# 5_USB-RTC-RST.net
KiCad netlist of a schematic drawn in Altium Designer
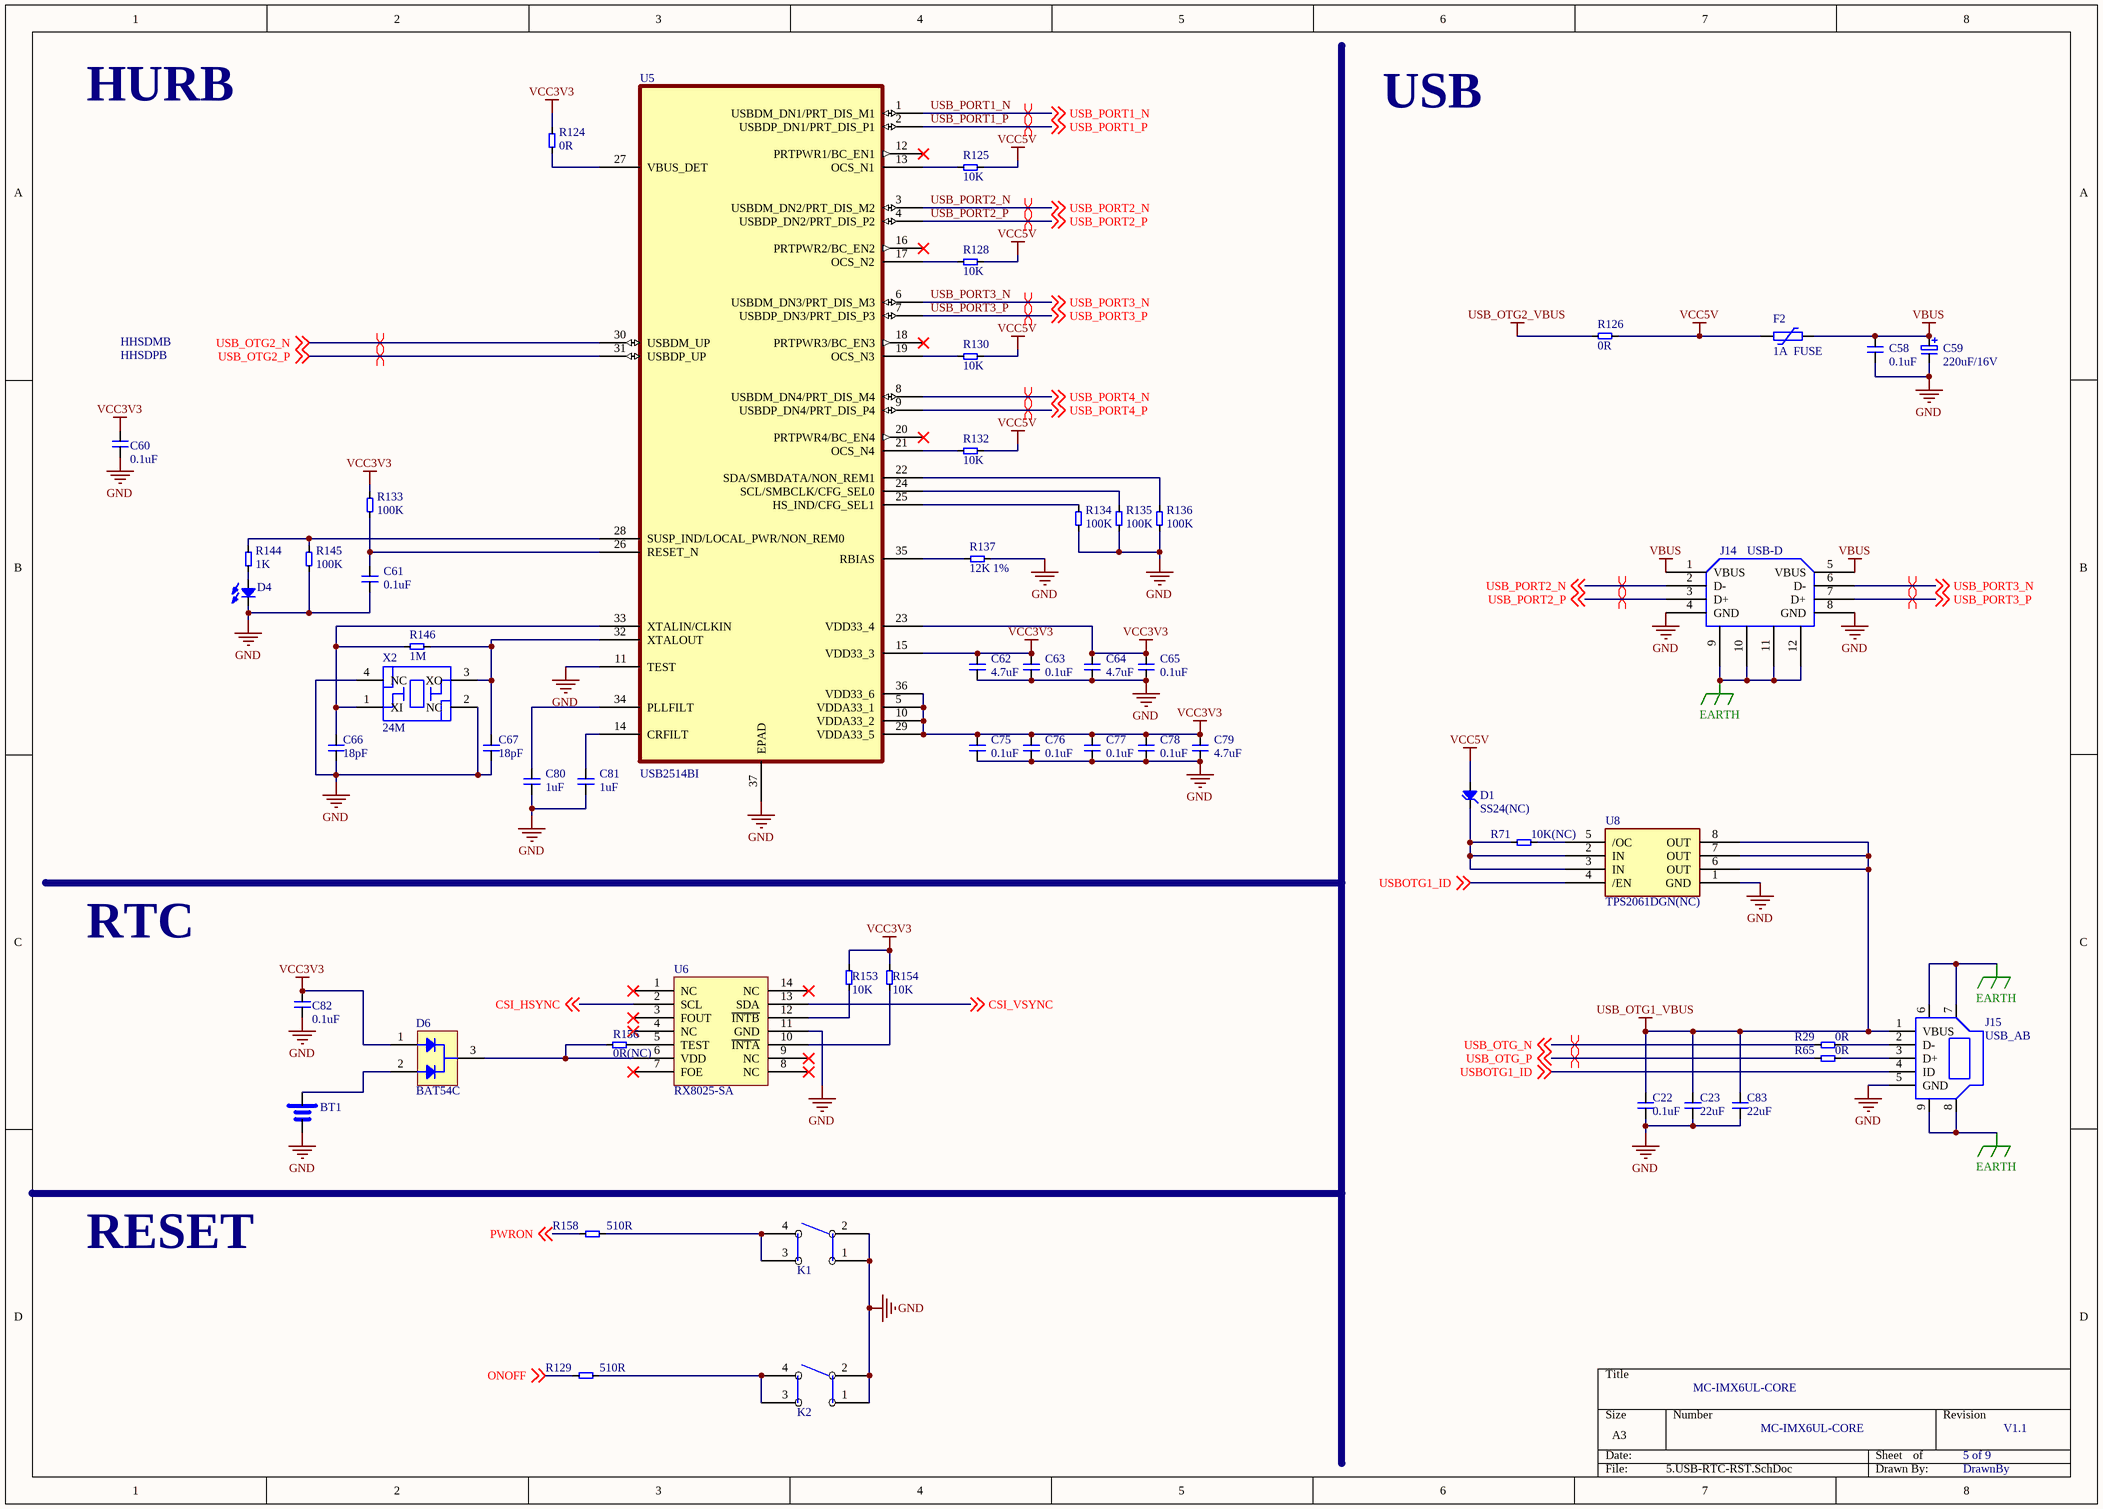
[diagram p0: 5.USB-RTC-RST.SchDoc]

(export (version "E")
  (design (tool "Eeschema 10.0.6"))
  (components
    (comp (ref "BT1") (value "~") (footprint "CR1220") (libsource (lib "LDT-SCH") (part "电池")))
    (comp (ref "C22")
      (value "0.1uF")
      (footprint "0603C")
      (description "电容")
      (libsource (lib "*") (part "电容"))
    )
    (comp (ref "C23") (value "22uF") (footprint "0805C") (description "电容") (libsource (lib "*") (part "电容")))
    (comp (ref "C58")
      (value "0.1uF")
      (footprint "0603C")
      (description "电容")
      (libsource (lib "*") (part "电容"))
    )
    (comp (ref "C59")
      (value "220uF/16V")
      (footprint "RAD-3/6")
      (description "直插电解电容")
      (libsource (lib "*") (part "直插电解电容"))
    )
    (comp (ref "C60")
      (value "0.1uF")
      (footprint "0603C")
      (description "电容")
      (libsource (lib "*") (part "电容"))
    )
    (comp (ref "C61")
      (value "0.1uF")
      (footprint "0603C")
      (description "电容")
      (libsource (lib "*") (part "电容"))
    )
    (comp (ref "C62")
      (value "4.7uF")
      (footprint "0603C")
      (description "电容")
      (libsource (lib "*") (part "电容"))
    )
    (comp (ref "C63")
      (value "0.1uF")
      (footprint "0603C")
      (description "电容")
      (libsource (lib "*") (part "电容"))
    )
    (comp (ref "C64")
      (value "4.7uF")
      (footprint "0603C")
      (description "电容")
      (libsource (lib "*") (part "电容"))
    )
    (comp (ref "C65")
      (value "0.1uF")
      (footprint "0603C")
      (description "电容")
      (libsource (lib "*") (part "电容"))
    )
    (comp (ref "C66") (value "18pF") (footprint "0603C") (description "电容") (libsource (lib "*") (part "电容")))
    (comp (ref "C67") (value "18pF") (footprint "0603C") (description "电容") (libsource (lib "*") (part "电容")))
    (comp (ref "C75")
      (value "0.1uF")
      (footprint "0603C")
      (description "电容")
      (libsource (lib "*") (part "电容"))
    )
    (comp (ref "C76")
      (value "0.1uF")
      (footprint "0603C")
      (description "电容")
      (libsource (lib "*") (part "电容"))
    )
    (comp (ref "C77")
      (value "0.1uF")
      (footprint "0603C")
      (description "电容")
      (libsource (lib "*") (part "电容"))
    )
    (comp (ref "C78")
      (value "0.1uF")
      (footprint "0603C")
      (description "电容")
      (libsource (lib "*") (part "电容"))
    )
    (comp (ref "C79")
      (value "4.7uF")
      (footprint "0603C")
      (description "电容")
      (libsource (lib "*") (part "电容"))
    )
    (comp (ref "C80") (value "1uF") (footprint "0603C") (description "电容") (libsource (lib "*") (part "电容")))
    (comp (ref "C81") (value "1uF") (footprint "0603C") (description "电容") (libsource (lib "*") (part "电容")))
    (comp (ref "C82")
      (value "0.1uF")
      (footprint "0603C")
      (description "电容")
      (libsource (lib "*") (part "电容"))
    )
    (comp (ref "C83") (value "22uF") (footprint "0805C") (description "电容") (libsource (lib "*") (part "电容")))
    (comp (ref "D1") (value "SS24(NC)") (footprint "SMA") (libsource (lib "LDT-SCH") (part "SS24")))
    (comp (ref "D4") (value "发光二极管") (footprint "0603D") (libsource (lib "LDT-SCH") (part "发光二极管")))
    (comp (ref "D6")
      (value "BAT54C")
      (footprint "SOT-23")
      (description "SCHOTTKY DIODE")
      (libsource (lib "LDT-SCH") (part "BAT54C"))
    )
    (comp (ref "F2")
      (value "1A  FUSE")
      (footprint "1812F")
      (description "贴片自恢复保险丝")
      (libsource (lib "LDT-SCH") (part "FUSE"))
    )
    (comp (ref "J14")
      (value "USB-D")
      (footprint "USB-D")
      (description "USB DOUBLE PORTS")
      (libsource (lib "LDT-SCH") (part "USB-D"))
    )
    (comp (ref "J15")
      (value "USB_AB")
      (footprint "USB-AB")
      (description "小USB插痤")
      (libsource (lib "LDT-SCH") (part "USB_AB"))
    )
    (comp (ref "K1") (value "按键") (footprint "SS-SPB-4.5") (libsource (lib "LDT-SCH") (part "按键")))
    (comp (ref "K2") (value "按键") (footprint "SS-SPB-4.5") (libsource (lib "LDT-SCH") (part "按键")))
    (comp (ref "R29")
      (value "0R")
      (footprint "0603R")
      (description "电阻")
      (libsource (lib "LDT-SCH") (part "电阻"))
    )
    (comp (ref "R65")
      (value "0R")
      (footprint "0603R")
      (description "电阻")
      (libsource (lib "LDT-SCH") (part "电阻"))
    )
    (comp (ref "R71")
      (value "10K(NC)")
      (footprint "0603R")
      (description "电阻")
      (libsource (lib "LDT-SCH") (part "电阻"))
    )
    (comp (ref "R124")
      (value "0R")
      (footprint "0603R")
      (description "电阻")
      (libsource (lib "LDT-SCH") (part "电阻"))
    )
    (comp (ref "R125")
      (value "10K")
      (footprint "0603R")
      (description "电阻")
      (libsource (lib "LDT-SCH") (part "电阻"))
    )
    (comp (ref "R126") (value "0R") (footprint "0603R") (description "电阻") (libsource (lib "*") (part "电阻")))
    (comp (ref "R128")
      (value "10K")
      (footprint "0603R")
      (description "电阻")
      (libsource (lib "LDT-SCH") (part "电阻"))
    )
    (comp (ref "R129")
      (value "510R")
      (footprint "0603R")
      (description "电阻")
      (libsource (lib "*") (part "电阻"))
    )
    (comp (ref "R130")
      (value "10K")
      (footprint "0603R")
      (description "电阻")
      (libsource (lib "LDT-SCH") (part "电阻"))
    )
    (comp (ref "R132")
      (value "10K")
      (footprint "0603R")
      (description "电阻")
      (libsource (lib "LDT-SCH") (part "电阻"))
    )
    (comp (ref "R133")
      (value "100K")
      (footprint "0603R")
      (description "电阻")
      (libsource (lib "LDT-SCH") (part "电阻"))
    )
    (comp (ref "R134")
      (value "100K")
      (footprint "0603R")
      (description "电阻")
      (libsource (lib "LDT-SCH") (part "电阻"))
    )
    (comp (ref "R135")
      (value "100K")
      (footprint "0603R")
      (description "电阻")
      (libsource (lib "LDT-SCH") (part "电阻"))
    )
    (comp (ref "R136")
      (value "100K")
      (footprint "0603R")
      (description "电阻")
      (libsource (lib "LDT-SCH") (part "电阻"))
    )
    (comp (ref "R137")
      (value "12K 1%")
      (footprint "0603R")
      (description "电阻")
      (libsource (lib "LDT-SCH") (part "电阻"))
    )
    (comp (ref "R144")
      (value "1K")
      (footprint "0603R")
      (description "电阻")
      (libsource (lib "LDT-SCH") (part "电阻"))
    )
    (comp (ref "R145")
      (value "100K")
      (footprint "0603R")
      (description "电阻")
      (libsource (lib "LDT-SCH") (part "电阻"))
    )
    (comp (ref "R146")
      (value "1M")
      (footprint "0603R")
      (description "电阻")
      (libsource (lib "LDT-SCH") (part "电阻"))
    )
    (comp (ref "R153") (value "10K") (footprint "0603R") (description "电阻") (libsource (lib "*") (part "电阻")))
    (comp (ref "R154") (value "10K") (footprint "0603R") (description "电阻") (libsource (lib "*") (part "电阻")))
    (comp (ref "R156")
      (value "0R(NC)")
      (footprint "0603R")
      (description "电阻")
      (libsource (lib "*") (part "电阻"))
    )
    (comp (ref "R158")
      (value "510R")
      (footprint "0603R")
      (description "电阻")
      (libsource (lib "*") (part "电阻"))
    )
    (comp (ref "U5")
      (value "USB2514BI")
      (footprint "QFN-36")
      (description "USB2514Bi")
      (libsource (lib "LDT-SCH") (part "USB2514"))
    )
    (comp (ref "U6")
      (value "RX8025-SA")
      (footprint "SOP14-1.27")
      (description "I2C interface RTC with crystal built-in")
      (libsource (lib "*") (part "RX8025-SA"))
    )
    (comp (ref "U8")
      (value "TPS2061DGN(NC)")
      (footprint "MSOP-8")
      (description "TPS2061DGN")
      (libsource (lib "LDT-SCH") (part "TPS2061"))
    )
    (comp (ref "X2")
      (value "24M")
      (footprint "OSC4-3225")
      (description "4PIN表贴晶体")
      (libsource (lib "LDT-SCH") (part "表贴晶体"))
    )
  )
  (nets
    (net (code "1") (name "CSI_HSYNC") (class "Default")
      (node (ref "U6") (pin "2") (pinfunction "SCL_2") (pintype "passive"))
    )
    (net (code "2") (name "CSI_VSYNC") (class "Default")
      (node (ref "U6") (pin "13") (pinfunction "SDA_13") (pintype "passive"))
    )
    (net (code "3") (name "EARTH") (class "Default")
      (node (ref "J14") (pin "10") (pintype "passive"))
      (node (ref "J14") (pin "11") (pintype "passive"))
      (node (ref "J14") (pin "12") (pintype "passive"))
      (node (ref "J14") (pin "9") (pintype "passive"))
      (node (ref "J15") (pin "6") (pinfunction "GND_6") (pintype "passive"))
      (node (ref "J15") (pin "7") (pinfunction "GND_7") (pintype "passive"))
      (node (ref "J15") (pin "8") (pinfunction "GND_8") (pintype "passive"))
      (node (ref "J15") (pin "9") (pinfunction "GND_9") (pintype "passive"))
    )
    (net (code "4") (name "GND") (class "Default")
      (node (ref "BT1") (pin "2") (pintype "passive"))
      (node (ref "C22") (pin "1") (pintype "passive"))
      (node (ref "C23") (pin "1") (pintype "passive"))
      (node (ref "C58") (pin "1") (pintype "passive"))
      (node (ref "C59") (pin "2") (pintype "passive"))
      (node (ref "C60") (pin "1") (pintype "passive"))
      (node (ref "C61") (pin "1") (pintype "passive"))
      (node (ref "C62") (pin "1") (pintype "passive"))
      (node (ref "C63") (pin "1") (pintype "passive"))
      (node (ref "C64") (pin "1") (pintype "passive"))
      (node (ref "C65") (pin "1") (pintype "passive"))
      (node (ref "C66") (pin "1") (pintype "passive"))
      (node (ref "C67") (pin "1") (pintype "passive"))
      (node (ref "C75") (pin "1") (pintype "passive"))
      (node (ref "C76") (pin "1") (pintype "passive"))
      (node (ref "C77") (pin "1") (pintype "passive"))
      (node (ref "C78") (pin "1") (pintype "passive"))
      (node (ref "C79") (pin "1") (pintype "passive"))
      (node (ref "C80") (pin "1") (pintype "passive"))
      (node (ref "C81") (pin "1") (pintype "passive"))
      (node (ref "C82") (pin "1") (pintype "passive"))
      (node (ref "C83") (pin "1") (pintype "passive"))
      (node (ref "D4") (pin "K") (pintype "passive"))
      (node (ref "J14") (pin "4") (pinfunction "GND_4") (pintype "passive"))
      (node (ref "J14") (pin "8") (pinfunction "GND_8") (pintype "passive"))
      (node (ref "J15") (pin "5") (pinfunction "GND_5") (pintype "passive"))
      (node (ref "K1") (pin "1") (pinfunction "1_1") (pintype "passive"))
      (node (ref "K1") (pin "2") (pinfunction "2_2") (pintype "passive"))
      (node (ref "K2") (pin "1") (pinfunction "1_1") (pintype "passive"))
      (node (ref "K2") (pin "2") (pinfunction "2_2") (pintype "passive"))
      (node (ref "R134") (pin "2") (pintype "passive"))
      (node (ref "R135") (pin "2") (pintype "passive"))
      (node (ref "R136") (pin "2") (pintype "passive"))
      (node (ref "R137") (pin "1") (pintype "passive"))
      (node (ref "R145") (pin "2") (pintype "passive"))
      (node (ref "U5") (pin "11") (pinfunction "TEST_11") (pintype "passive"))
      (node (ref "U5") (pin "37") (pinfunction "EPAD_37") (pintype "passive"))
      (node (ref "U6") (pin "11") (pinfunction "GND_11") (pintype "passive"))
      (node (ref "U8") (pin "1") (pinfunction "GND_1") (pintype "passive"))
      (node (ref "X2") (pin "2") (pinfunction "NC_2") (pintype "passive"))
      (node (ref "X2") (pin "4") (pinfunction "NC_4") (pintype "passive"))
    )
    (net (code "5") (name "Net-(BT1-Pad1)") (class "Default")
      (node (ref "BT1") (pin "1") (pintype "passive"))
      (node (ref "D6") (pin "2") (pinfunction "2_2") (pintype "passive"))
    )
    (net (code "6") (name "Net-(D1-PadK)") (class "Default")
      (node (ref "D1") (pin "K") (pintype "passive"))
      (node (ref "R71") (pin "2") (pintype "passive"))
      (node (ref "U8") (pin "2") (pinfunction "IN_2") (pintype "passive"))
      (node (ref "U8") (pin "3") (pinfunction "IN_3") (pintype "passive"))
    )
    (net (code "7") (name "Net-(D4-PadA)") (class "Default")
      (node (ref "D4") (pin "A") (pintype "passive"))
      (node (ref "R144") (pin "1") (pintype "passive"))
    )
    (net (code "8") (name "Net-(J15-D+)") (class "Default")
      (node (ref "J15") (pin "3") (pinfunction "D+_3") (pintype "passive"))
      (node (ref "R65") (pin "1") (pintype "passive"))
    )
    (net (code "9") (name "Net-(J15-D-)") (class "Default")
      (node (ref "J15") (pin "2") (pinfunction "D-_2") (pintype "passive"))
      (node (ref "R29") (pin "1") (pintype "passive"))
    )
    (net (code "10") (name "Net-(K1-Pad3)") (class "Default")
      (node (ref "K1") (pin "3") (pinfunction "3_3") (pintype "passive"))
      (node (ref "K1") (pin "4") (pinfunction "4_4") (pintype "passive"))
      (node (ref "R158") (pin "1") (pintype "passive"))
    )
    (net (code "11") (name "Net-(K2-Pad3)") (class "Default")
      (node (ref "K2") (pin "3") (pinfunction "3_3") (pintype "passive"))
      (node (ref "K2") (pin "4") (pinfunction "4_4") (pintype "passive"))
      (node (ref "R129") (pin "1") (pintype "passive"))
    )
    (net (code "12") (name "Net-(U5-CRFILT)") (class "Default")
      (node (ref "C81") (pin "2") (pintype "passive"))
      (node (ref "U5") (pin "14") (pinfunction "CRFILT_14") (pintype "passive"))
    )
    (net (code "13") (name "Net-(U5-HS_IND{slash}CFG_SEL1)") (class "Default")
      (node (ref "R134") (pin "1") (pintype "passive"))
      (node (ref "U5") (pin "25") (pinfunction "HS_IND/CFG_SEL1_25") (pintype "passive"))
    )
    (net (code "14") (name "Net-(U5-OCS_N1)") (class "Default")
      (node (ref "R125") (pin "2") (pintype "passive"))
      (node (ref "U5") (pin "13") (pinfunction "OCS_N1_13") (pintype "passive"))
    )
    (net (code "15") (name "Net-(U5-OCS_N2)") (class "Default")
      (node (ref "R128") (pin "2") (pintype "passive"))
      (node (ref "U5") (pin "17") (pinfunction "OCS_N2_17") (pintype "passive"))
    )
    (net (code "16") (name "Net-(U5-OCS_N3)") (class "Default")
      (node (ref "R130") (pin "2") (pintype "passive"))
      (node (ref "U5") (pin "19") (pinfunction "OCS_N3_19") (pintype "passive"))
    )
    (net (code "17") (name "Net-(U5-OCS_N4)") (class "Default")
      (node (ref "R132") (pin "2") (pintype "passive"))
      (node (ref "U5") (pin "21") (pinfunction "OCS_N4_21") (pintype "passive"))
    )
    (net (code "18") (name "Net-(U5-PLLFILT)") (class "Default")
      (node (ref "C80") (pin "2") (pintype "passive"))
      (node (ref "U5") (pin "34") (pinfunction "PLLFILT_34") (pintype "passive"))
    )
    (net (code "19") (name "Net-(U5-RBIAS)") (class "Default")
      (node (ref "R137") (pin "2") (pintype "passive"))
      (node (ref "U5") (pin "35") (pinfunction "RBIAS_35") (pintype "passive"))
    )
    (net (code "20") (name "Net-(U5-RESET_N)") (class "Default")
      (node (ref "C61") (pin "2") (pintype "passive"))
      (node (ref "R133") (pin "2") (pintype "passive"))
      (node (ref "U5") (pin "26") (pinfunction "RESET_N_26") (pintype "passive"))
    )
    (net (code "21") (name "Net-(U5-SCL{slash}SMBCLK{slash}CFG_SEL0)") (class "Default")
      (node (ref "R135") (pin "1") (pintype "passive"))
      (node (ref "U5") (pin "24") (pinfunction "SCL/SMBCLK/CFG_SEL0_24") (pintype "passive"))
    )
    (net (code "22") (name "Net-(U5-SDA{slash}SMBDATA{slash}NON_REM1)") (class "Default")
      (node (ref "R136") (pin "1") (pintype "passive"))
      (node (ref "U5") (pin "22") (pinfunction "SDA/SMBDATA/NON_REM1_22") (pintype "passive"))
    )
    (net (code "23") (name "Net-(U5-SUSP_IND{slash}LOCAL_PWR{slash}NON_REM0)") (class "Default")
      (node (ref "R144") (pin "2") (pintype "passive"))
      (node (ref "R145") (pin "1") (pintype "passive"))
      (node (ref "U5") (pin "28") (pinfunction "SUSP_IND/LOCAL_PWR/NON_REM0_28") (pintype "passive"))
    )
    (net (code "24") (name "Net-(U5-VBUS_DET)") (class "Default")
      (node (ref "R124") (pin "1") (pintype "passive"))
      (node (ref "U5") (pin "27") (pinfunction "VBUS_DET_27") (pintype "passive"))
    )
    (net (code "25") (name "Net-(U5-XTALIN{slash}CLKIN)") (class "Default")
      (node (ref "C66") (pin "2") (pintype "passive"))
      (node (ref "R146") (pin "1") (pintype "passive"))
      (node (ref "U5") (pin "33") (pinfunction "XTALIN/CLKIN_33") (pintype "passive"))
      (node (ref "X2") (pin "1") (pinfunction "XI_1") (pintype "passive"))
    )
    (net (code "26") (name "Net-(U5-XTALOUT)") (class "Default")
      (node (ref "C67") (pin "2") (pintype "passive"))
      (node (ref "R146") (pin "2") (pintype "passive"))
      (node (ref "U5") (pin "32") (pinfunction "XTALOUT_32") (pintype "passive"))
      (node (ref "X2") (pin "3") (pinfunction "XO_3") (pintype "passive"))
    )
    (net (code "27") (name "Net-(U6-TEST)") (class "Default")
      (node (ref "R156") (pin "1") (pintype "passive"))
      (node (ref "U6") (pin "5") (pinfunction "TEST_5") (pintype "passive"))
    )
    (net (code "28") (name "Net-(U6-VDD)") (class "Default")
      (node (ref "D6") (pin "3") (pinfunction "3_3") (pintype "passive"))
      (node (ref "R156") (pin "2") (pintype "passive"))
      (node (ref "U6") (pin "6") (pinfunction "VDD_6") (pintype "passive"))
    )
    (net (code "29") (name "Net-(U6-~{INTA})") (class "Default")
      (node (ref "R154") (pin "1") (pintype "passive"))
      (node (ref "U6") (pin "10") (pinfunction "~{INTA}_10") (pintype "passive"))
    )
    (net (code "30") (name "Net-(U6-~{INTB})") (class "Default")
      (node (ref "R153") (pin "1") (pintype "passive"))
      (node (ref "U6") (pin "12") (pinfunction "~{INTB}_12") (pintype "passive"))
    )
    (net (code "31") (name "Net-(U8-{slash}OC)") (class "Default")
      (node (ref "R71") (pin "1") (pintype "passive"))
      (node (ref "U8") (pin "5") (pinfunction "/OC_5") (pintype "passive"))
    )
    (net (code "32") (name "ONOFF") (class "Default") (node (ref "R129") (pin "2") (pintype "passive")))
    (net (code "33") (name "PWRON") (class "Default") (node (ref "R158") (pin "2") (pintype "passive")))
    (net (code "34") (name "USBOTG1_ID") (class "Default")
      (node (ref "J15") (pin "4") (pinfunction "ID_4") (pintype "passive"))
      (node (ref "U8") (pin "4") (pinfunction "/EN_4") (pintype "passive"))
    )
    (net (code "35") (name "USB_OTG1_VBUS") (class "Default")
      (node (ref "C22") (pin "2") (pintype "passive"))
      (node (ref "C23") (pin "2") (pintype "passive"))
      (node (ref "C83") (pin "2") (pintype "passive"))
      (node (ref "J15") (pin "1") (pinfunction "VBUS_1") (pintype "passive"))
      (node (ref "U8") (pin "6") (pinfunction "OUT_6") (pintype "passive"))
      (node (ref "U8") (pin "7") (pinfunction "OUT_7") (pintype "passive"))
      (node (ref "U8") (pin "8") (pinfunction "OUT_8") (pintype "passive"))
    )
    (net (code "36") (name "USB_OTG2_N") (class "Default")
      (node (ref "U5") (pin "30") (pinfunction "USBDM_UP_30") (pintype "bidirectional"))
    )
    (net (code "37") (name "USB_OTG2_P") (class "Default")
      (node (ref "U5") (pin "31") (pinfunction "USBDP_UP_31") (pintype "bidirectional"))
    )
    (net (code "38") (name "USB_OTG2_VBUS") (class "Default")
      (node (ref "R126") (pin "2") (pintype "passive"))
    )
    (net (code "39") (name "USB_OTG_N") (class "Default") (node (ref "R29") (pin "2") (pintype "passive")))
    (net (code "40") (name "USB_OTG_P") (class "Default") (node (ref "R65") (pin "2") (pintype "passive")))
    (net (code "41") (name "USB_PORT1_N") (class "Default")
      (node (ref "U5") (pin "1") (pinfunction "USBDM_DN1/PRT_DIS_M1_1") (pintype "bidirectional"))
    )
    (net (code "42") (name "USB_PORT1_P") (class "Default")
      (node (ref "U5") (pin "2") (pinfunction "USBDP_DN1/PRT_DIS_P1_2") (pintype "bidirectional"))
    )
    (net (code "43") (name "USB_PORT2_N") (class "Default")
      (node (ref "J14") (pin "2") (pinfunction "D-_2") (pintype "passive"))
      (node (ref "U5") (pin "3") (pinfunction "USBDM_DN2/PRT_DIS_M2_3") (pintype "bidirectional"))
    )
    (net (code "44") (name "USB_PORT2_P") (class "Default")
      (node (ref "J14") (pin "3") (pinfunction "D+_3") (pintype "passive"))
      (node (ref "U5") (pin "4") (pinfunction "USBDP_DN2/PRT_DIS_P2_4") (pintype "bidirectional"))
    )
    (net (code "45") (name "USB_PORT3_N") (class "Default")
      (node (ref "J14") (pin "6") (pinfunction "D-_6") (pintype "passive"))
      (node (ref "U5") (pin "6") (pinfunction "USBDM_DN3/PRT_DIS_M3_6") (pintype "bidirectional"))
    )
    (net (code "46") (name "USB_PORT3_P") (class "Default")
      (node (ref "J14") (pin "7") (pinfunction "D+_7") (pintype "passive"))
      (node (ref "U5") (pin "7") (pinfunction "USBDP_DN3/PRT_DIS_P3_7") (pintype "bidirectional"))
    )
    (net (code "47") (name "USB_PORT4_N") (class "Default")
      (node (ref "U5") (pin "8") (pinfunction "USBDM_DN4/PRT_DIS_M4_8") (pintype "bidirectional"))
    )
    (net (code "48") (name "USB_PORT4_P") (class "Default")
      (node (ref "U5") (pin "9") (pinfunction "USBDP_DN4/PRT_DIS_P4_9") (pintype "bidirectional"))
    )
    (net (code "49") (name "VBUS") (class "Default")
      (node (ref "C58") (pin "2") (pintype "passive"))
      (node (ref "C59") (pin "1") (pintype "passive"))
      (node (ref "F2") (pin "2") (pinfunction "2_2") (pintype "passive"))
      (node (ref "J14") (pin "1") (pinfunction "VBUS_1") (pintype "passive"))
      (node (ref "J14") (pin "5") (pinfunction "VBUS_5") (pintype "passive"))
    )
    (net (code "50") (name "VCC3V3") (class "Default")
      (node (ref "C60") (pin "2") (pintype "passive"))
      (node (ref "C62") (pin "2") (pintype "passive"))
      (node (ref "C63") (pin "2") (pintype "passive"))
      (node (ref "C64") (pin "2") (pintype "passive"))
      (node (ref "C65") (pin "2") (pintype "passive"))
      (node (ref "C75") (pin "2") (pintype "passive"))
      (node (ref "C76") (pin "2") (pintype "passive"))
      (node (ref "C77") (pin "2") (pintype "passive"))
      (node (ref "C78") (pin "2") (pintype "passive"))
      (node (ref "C79") (pin "2") (pintype "passive"))
      (node (ref "C82") (pin "2") (pintype "passive"))
      (node (ref "D6") (pin "1") (pinfunction "1_1") (pintype "passive"))
      (node (ref "R124") (pin "2") (pintype "passive"))
      (node (ref "R133") (pin "1") (pintype "passive"))
      (node (ref "R153") (pin "2") (pintype "passive"))
      (node (ref "R154") (pin "2") (pintype "passive"))
      (node (ref "U5") (pin "10") (pinfunction "VDDA33_2_10") (pintype "passive"))
      (node (ref "U5") (pin "15") (pinfunction "VDD33_3_15") (pintype "passive"))
      (node (ref "U5") (pin "23") (pinfunction "VDD33_4_23") (pintype "passive"))
      (node (ref "U5") (pin "29") (pinfunction "VDDA33_5_29") (pintype "passive"))
      (node (ref "U5") (pin "36") (pinfunction "VDD33_6_36") (pintype "passive"))
      (node (ref "U5") (pin "5") (pinfunction "VDDA33_1_5") (pintype "passive"))
    )
    (net (code "51") (name "VCC5V") (class "Default")
      (node (ref "D1") (pin "A") (pintype "passive"))
      (node (ref "F2") (pin "1") (pinfunction "1_1") (pintype "passive"))
      (node (ref "R125") (pin "1") (pintype "passive"))
      (node (ref "R126") (pin "1") (pintype "passive"))
      (node (ref "R128") (pin "1") (pintype "passive"))
      (node (ref "R130") (pin "1") (pintype "passive"))
      (node (ref "R132") (pin "1") (pintype "passive"))
    )
    (net (code "52") (name "unconnected-(U5-PRTPWR1{slash}BC_EN1-Pad12)") (class "Default")
      (node (ref "U5") (pin "12") (pinfunction "PRTPWR1/BC_EN1_12") (pintype "output+no_connect"))
    )
    (net (code "53") (name "unconnected-(U5-PRTPWR2{slash}BC_EN2-Pad16)") (class "Default")
      (node (ref "U5") (pin "16") (pinfunction "PRTPWR2/BC_EN2_16") (pintype "output+no_connect"))
    )
    (net (code "54") (name "unconnected-(U5-PRTPWR3{slash}BC_EN3-Pad18)") (class "Default")
      (node (ref "U5") (pin "18") (pinfunction "PRTPWR3/BC_EN3_18") (pintype "output+no_connect"))
    )
    (net (code "55") (name "unconnected-(U5-PRTPWR4{slash}BC_EN4-Pad20)") (class "Default")
      (node (ref "U5") (pin "20") (pinfunction "PRTPWR4/BC_EN4_20") (pintype "output+no_connect"))
    )
    (net (code "56") (name "unconnected-(U6-FOE-Pad7)") (class "Default")
      (node (ref "U6") (pin "7") (pinfunction "FOE_7") (pintype "passive+no_connect"))
    )
    (net (code "57") (name "unconnected-(U6-FOUT-Pad3)") (class "Default")
      (node (ref "U6") (pin "3") (pinfunction "FOUT_3") (pintype "passive+no_connect"))
    )
    (net (code "58") (name "unconnected-(U6-NC-Pad1)") (class "Default")
      (node (ref "U6") (pin "1") (pinfunction "NC_1") (pintype "passive+no_connect"))
    )
    (net (code "59") (name "unconnected-(U6-NC-Pad4)") (class "Default")
      (node (ref "U6") (pin "4") (pinfunction "NC_4") (pintype "passive+no_connect"))
    )
    (net (code "60") (name "unconnected-(U6-NC-Pad8)") (class "Default")
      (node (ref "U6") (pin "8") (pinfunction "NC_8") (pintype "passive+no_connect"))
    )
    (net (code "61") (name "unconnected-(U6-NC-Pad9)") (class "Default")
      (node (ref "U6") (pin "9") (pinfunction "NC_9") (pintype "passive+no_connect"))
    )
    (net (code "62") (name "unconnected-(U6-NC-Pad14)") (class "Default")
      (node (ref "U6") (pin "14") (pinfunction "NC_14") (pintype "passive+no_connect"))
    )
  )
)
